# v2_1.net
KiCad netlist of a schematic drawn in EAGLE
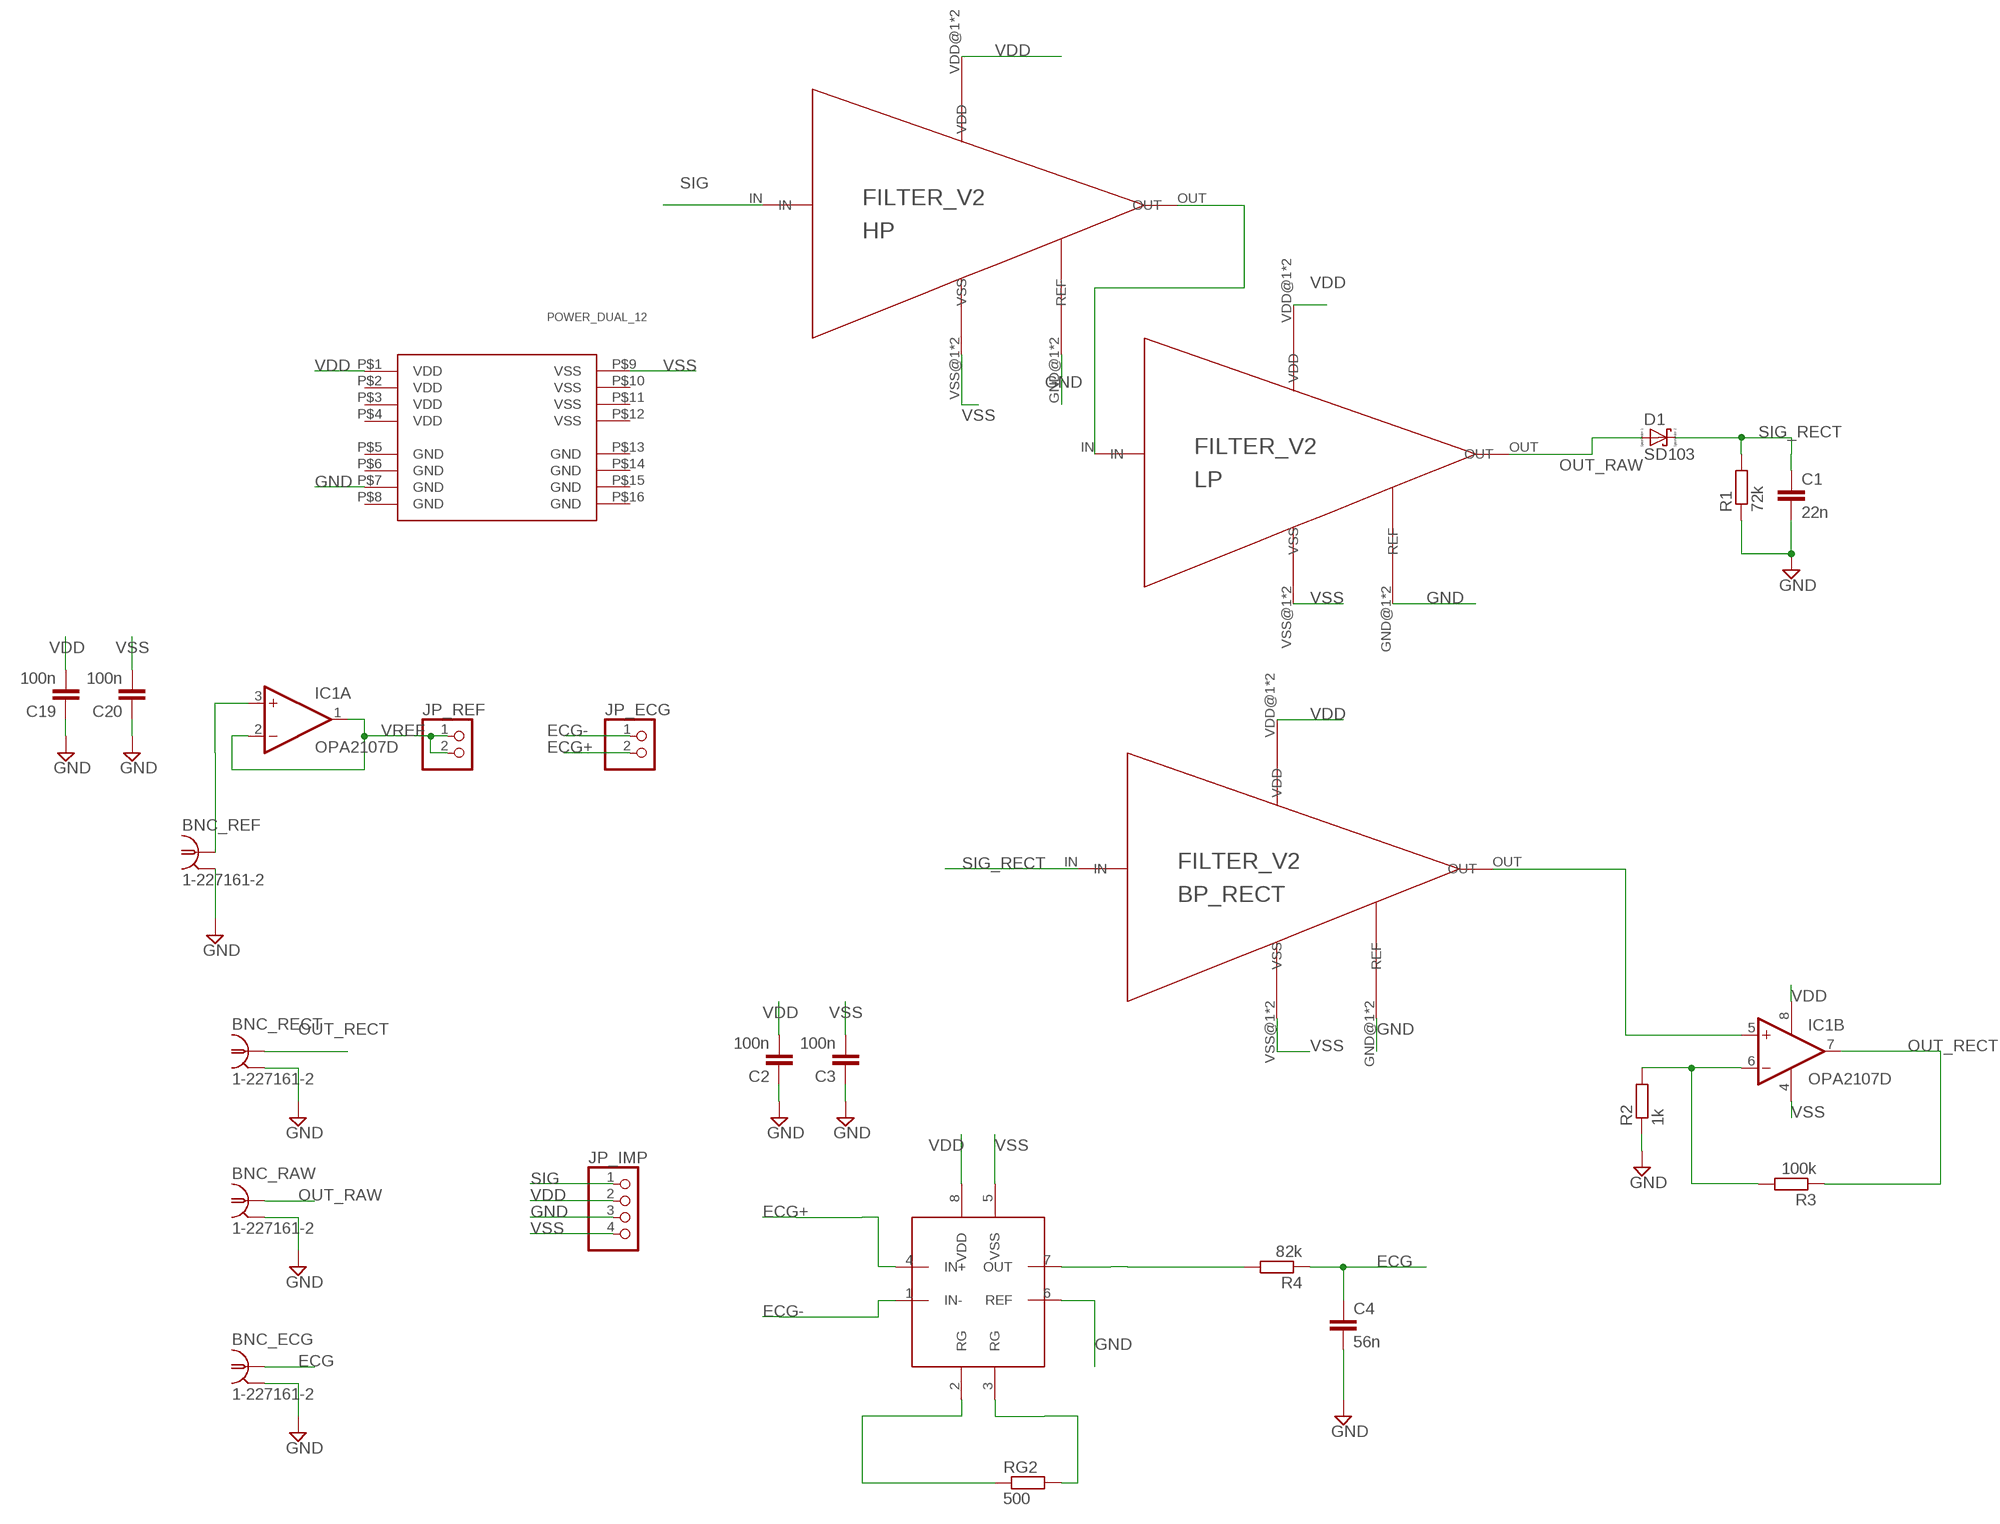
[diagram p0: schematic, sheet 1]

(export (version "E")
  (design (tool "Eeschema 10.0.6"))
  (components
    (comp (ref "BNC_ECG")
      (value "1-227161-2")
      (footprint "eagle-import:AMP_227161")
      (libsource (lib "eagle-import") (part "?2271611--2"))
    )
    (comp (ref "BNC_RAW")
      (value "1-227161-2")
      (footprint "eagle-import:AMP_227161")
      (libsource (lib "eagle-import") (part "?2271611--2"))
    )
    (comp (ref "BNC_RECT")
      (value "1-227161-2")
      (footprint "eagle-import:AMP_227161")
      (libsource (lib "eagle-import") (part "?2271611--2"))
    )
    (comp (ref "BNC_REF")
      (value "1-227161-2")
      (footprint "eagle-import:AMP_227161")
      (libsource (lib "eagle-import") (part "?2271611--2"))
    )
    (comp (ref "BP_RECT")
      (value "FILTER_V2")
      (footprint "eagle-import:MODULE_FILTER_V2")
      (libsource (lib "eagle-import") (part "FILTER_V2"))
    )
    (comp (ref "C1")
      (value "22n")
      (footprint "eagle-import:C0805")
      (libsource (lib "eagle-import") (part "C-EUC0805"))
    )
    (comp (ref "C2")
      (value "100n")
      (footprint "eagle-import:C0805")
      (libsource (lib "eagle-import") (part "resistor_348_C-EUC0805"))
    )
    (comp (ref "C3")
      (value "100n")
      (footprint "eagle-import:C0805")
      (libsource (lib "eagle-import") (part "resistor_348_C-EUC0805"))
    )
    (comp (ref "C4")
      (value "56n")
      (footprint "eagle-import:C0805")
      (libsource (lib "eagle-import") (part "C-EUC0805"))
    )
    (comp (ref "C19")
      (value "100n")
      (footprint "eagle-import:C0805")
      (libsource (lib "eagle-import") (part "resistor_348_C-EUC0805"))
    )
    (comp (ref "C20")
      (value "100n")
      (footprint "eagle-import:C0805")
      (libsource (lib "eagle-import") (part "resistor_348_C-EUC0805"))
    )
    (comp (ref "D1")
      (value "SD103")
      (footprint "eagle-import:DIODE_SMB")
      (libsource (lib "eagle-import") (part "SCHOTTKY-DIODE"))
    )
    (comp (ref "HP")
      (value "FILTER_V2")
      (footprint "eagle-import:MODULE_FILTER_V2")
      (libsource (lib "eagle-import") (part "FILTER_V2"))
    )
    (comp (ref "IC1")
      (value "OPA2107D")
      (footprint "eagle-import:SO08")
      (libsource (lib "eagle-import") (part "OPA2107D"))
    )
    (comp (ref "INA")
      (value "AD8429")
      (footprint "eagle-import:SO8")
      (libsource (lib "eagle-import") (part "AD8429"))
    )
    (comp (ref "JP_ECG")
      (value "PINHD-1X2")
      (footprint "eagle-import:1X02")
      (libsource (lib "eagle-import") (part "PINHD-1X2"))
    )
    (comp (ref "JP_IMP")
      (value "PINHD-1X4")
      (footprint "eagle-import:1X04")
      (libsource (lib "eagle-import") (part "PINHD-1X4"))
    )
    (comp (ref "JP_REF")
      (value "PINHD-1X2")
      (footprint "eagle-import:1X02")
      (libsource (lib "eagle-import") (part "PINHD-1X2"))
    )
    (comp (ref "LP")
      (value "FILTER_V2")
      (footprint "eagle-import:MODULE_FILTER_V2")
      (libsource (lib "eagle-import") (part "FILTER_V2"))
    )
    (comp (ref "R1")
      (value "72k")
      (footprint "eagle-import:R0805")
      (libsource (lib "eagle-import") (part "R-EU_R0805"))
    )
    (comp (ref "R2")
      (value "1k")
      (footprint "eagle-import:R0805")
      (libsource (lib "eagle-import") (part "R-EU_R0805"))
    )
    (comp (ref "R3")
      (value "100k")
      (footprint "eagle-import:R0805")
      (libsource (lib "eagle-import") (part "R-EU_R0805"))
    )
    (comp (ref "R4")
      (value "82k")
      (footprint "eagle-import:R0805")
      (libsource (lib "eagle-import") (part "R-EU_R0805"))
    )
    (comp (ref "RG2")
      (value "500")
      (footprint "eagle-import:R0805")
      (libsource (lib "eagle-import") (part "R-EU_R0805"))
    )
    (comp (ref "U$1")
      (value "POWER_DUAL_12")
      (footprint "eagle-import:MODULE_4X8")
      (libsource (lib "eagle-import") (part "POWER_DUAL_12"))
    )
  )
  (nets
    (net (code "1") (name "/ECG") (class "Default")
      (node (ref "BNC_ECG") (pin "1") (pinfunction "1_1") (pintype "passive"))
      (node (ref "C4") (pin "1") (pinfunction "1_1") (pintype "passive"))
      (node (ref "R4") (pin "1") (pinfunction "1_1") (pintype "passive"))
    )
    (net (code "2") (name "/ECG+") (class "Default")
      (node (ref "INA") (pin "4") (pinfunction "IN+_4") (pintype "bidirectional"))
      (node (ref "JP_ECG") (pin "2") (pinfunction "2_2") (pintype "passive"))
    )
    (net (code "3") (name "/ECG-") (class "Default")
      (node (ref "INA") (pin "1") (pinfunction "IN-_1") (pintype "bidirectional"))
      (node (ref "JP_ECG") (pin "1") (pinfunction "1_1") (pintype "passive"))
    )
    (net (code "4") (name "/OUT_RAW") (class "Default")
      (node (ref "BNC_RAW") (pin "1") (pinfunction "1_1") (pintype "passive"))
      (node (ref "D1") (pin "A") (pinfunction "C_A") (pintype "passive"))
      (node (ref "LP") (pin "OUT") (pinfunction "OUT_OUT") (pintype "bidirectional"))
    )
    (net (code "5") (name "/OUT_RECT") (class "Default")
      (node (ref "BNC_RECT") (pin "1") (pinfunction "1_1") (pintype "passive"))
      (node (ref "IC1") (pin "7") (pinfunction "OUT_7") (pintype "output"))
      (node (ref "R3") (pin "1") (pinfunction "1_1") (pintype "passive"))
    )
    (net (code "6") (name "/SIG") (class "Default")
      (node (ref "HP") (pin "IN") (pinfunction "IN_IN") (pintype "bidirectional"))
      (node (ref "JP_IMP") (pin "1") (pinfunction "1_1") (pintype "passive"))
    )
    (net (code "7") (name "/SIG_RECT") (class "Default")
      (node (ref "BP_RECT") (pin "IN") (pinfunction "IN_IN") (pintype "bidirectional"))
      (node (ref "C1") (pin "1") (pinfunction "1_1") (pintype "passive"))
      (node (ref "D1") (pin "C") (pinfunction "A_C") (pintype "passive"))
      (node (ref "R1") (pin "2") (pinfunction "2_2") (pintype "passive"))
    )
    (net (code "8") (name "/VDD") (class "Default")
      (node (ref "BP_RECT") (pin "VDD@1") (pinfunction "VDD_VDD@1") (pintype "bidirectional"))
      (node (ref "BP_RECT") (pin "VDD@2") (pinfunction "VDD_VDD@2") (pintype "bidirectional"))
      (node (ref "C19") (pin "2") (pinfunction "2_2") (pintype "passive"))
      (node (ref "C2") (pin "2") (pinfunction "2_2") (pintype "passive"))
      (node (ref "HP") (pin "VDD@1") (pinfunction "VDD_VDD@1") (pintype "bidirectional"))
      (node (ref "HP") (pin "VDD@2") (pinfunction "VDD_VDD@2") (pintype "bidirectional"))
      (node (ref "IC1") (pin "8") (pinfunction "V+_8") (pintype "power_in"))
      (node (ref "INA") (pin "8") (pinfunction "VDD_8") (pintype "bidirectional"))
      (node (ref "JP_IMP") (pin "2") (pinfunction "2_2") (pintype "passive"))
      (node (ref "LP") (pin "VDD@1") (pinfunction "VDD_VDD@1") (pintype "bidirectional"))
      (node (ref "LP") (pin "VDD@2") (pinfunction "VDD_VDD@2") (pintype "bidirectional"))
      (node (ref "U$1") (pin "P$1") (pinfunction "VDD_P$1") (pintype "bidirectional"))
    )
    (net (code "9") (name "/VREF") (class "Default")
      (node (ref "IC1") (pin "1") (pinfunction "OUT_1") (pintype "output"))
      (node (ref "IC1") (pin "2") (pinfunction "-IN_2") (pintype "input"))
      (node (ref "JP_REF") (pin "1") (pinfunction "1_1") (pintype "passive"))
      (node (ref "JP_REF") (pin "2") (pinfunction "2_2") (pintype "passive"))
    )
    (net (code "10") (name "/VSS") (class "Default")
      (node (ref "BP_RECT") (pin "VSS@1") (pinfunction "VSS_VSS@1") (pintype "bidirectional"))
      (node (ref "BP_RECT") (pin "VSS@2") (pinfunction "VSS_VSS@2") (pintype "bidirectional"))
      (node (ref "C20") (pin "2") (pinfunction "2_2") (pintype "passive"))
      (node (ref "C3") (pin "2") (pinfunction "2_2") (pintype "passive"))
      (node (ref "HP") (pin "VSS@1") (pinfunction "VSS_VSS@1") (pintype "bidirectional"))
      (node (ref "HP") (pin "VSS@2") (pinfunction "VSS_VSS@2") (pintype "bidirectional"))
      (node (ref "IC1") (pin "4") (pinfunction "V-_4") (pintype "power_in"))
      (node (ref "INA") (pin "5") (pinfunction "VSS_5") (pintype "bidirectional"))
      (node (ref "JP_IMP") (pin "4") (pinfunction "4_4") (pintype "passive"))
      (node (ref "LP") (pin "VSS@1") (pinfunction "VSS_VSS@1") (pintype "bidirectional"))
      (node (ref "LP") (pin "VSS@2") (pinfunction "VSS_VSS@2") (pintype "bidirectional"))
      (node (ref "U$1") (pin "P$9") (pinfunction "VSS_P$9") (pintype "bidirectional"))
    )
    (net (code "11") (name "GND") (class "Default")
      (node (ref "BNC_ECG") (pin "2") (pinfunction "2_2") (pintype "passive"))
      (node (ref "BNC_RAW") (pin "2") (pinfunction "2_2") (pintype "passive"))
      (node (ref "BNC_RECT") (pin "2") (pinfunction "2_2") (pintype "passive"))
      (node (ref "BNC_REF") (pin "2") (pinfunction "2_2") (pintype "passive"))
      (node (ref "BP_RECT") (pin "GND@1") (pinfunction "REF_GND@1") (pintype "bidirectional"))
      (node (ref "BP_RECT") (pin "GND@2") (pinfunction "REF_GND@2") (pintype "bidirectional"))
      (node (ref "C1") (pin "2") (pinfunction "2_2") (pintype "passive"))
      (node (ref "C19") (pin "1") (pinfunction "1_1") (pintype "passive"))
      (node (ref "C2") (pin "1") (pinfunction "1_1") (pintype "passive"))
      (node (ref "C20") (pin "1") (pinfunction "1_1") (pintype "passive"))
      (node (ref "C3") (pin "1") (pinfunction "1_1") (pintype "passive"))
      (node (ref "C4") (pin "2") (pinfunction "2_2") (pintype "passive"))
      (node (ref "HP") (pin "GND@1") (pinfunction "REF_GND@1") (pintype "bidirectional"))
      (node (ref "HP") (pin "GND@2") (pinfunction "REF_GND@2") (pintype "bidirectional"))
      (node (ref "INA") (pin "6") (pinfunction "REF_6") (pintype "bidirectional"))
      (node (ref "JP_IMP") (pin "3") (pinfunction "3_3") (pintype "passive"))
      (node (ref "LP") (pin "GND@1") (pinfunction "REF_GND@1") (pintype "bidirectional"))
      (node (ref "LP") (pin "GND@2") (pinfunction "REF_GND@2") (pintype "bidirectional"))
      (node (ref "R1") (pin "1") (pinfunction "1_1") (pintype "passive"))
      (node (ref "R2") (pin "1") (pinfunction "1_1") (pintype "passive"))
      (node (ref "U$1") (pin "P$7") (pinfunction "GND_P$7") (pintype "bidirectional"))
    )
    (net (code "12") (name "Net-(HP-PadOUT)") (class "Default")
      (node (ref "HP") (pin "OUT") (pinfunction "OUT_OUT") (pintype "bidirectional"))
      (node (ref "LP") (pin "IN") (pinfunction "IN_IN") (pintype "bidirectional"))
    )
    (net (code "13") (name "Net-(IC1A-+IN)") (class "Default")
      (node (ref "BNC_REF") (pin "1") (pinfunction "1_1") (pintype "passive"))
      (node (ref "IC1") (pin "3") (pinfunction "+IN_3") (pintype "input"))
    )
    (net (code "14") (name "Net-(IC1B-+IN)") (class "Default")
      (node (ref "BP_RECT") (pin "OUT") (pinfunction "OUT_OUT") (pintype "bidirectional"))
      (node (ref "IC1") (pin "5") (pinfunction "+IN_5") (pintype "input"))
    )
    (net (code "15") (name "Net-(IC1B--IN)") (class "Default")
      (node (ref "IC1") (pin "6") (pinfunction "-IN_6") (pintype "input"))
      (node (ref "R2") (pin "2") (pinfunction "2_2") (pintype "passive"))
      (node (ref "R3") (pin "2") (pinfunction "2_2") (pintype "passive"))
    )
    (net (code "16") (name "Net-(INA-OUT)") (class "Default")
      (node (ref "INA") (pin "7") (pinfunction "OUT_7") (pintype "bidirectional"))
      (node (ref "R4") (pin "2") (pinfunction "2_2") (pintype "passive"))
    )
    (net (code "17") (name "Net-(INA-RG-Pad2)") (class "Default")
      (node (ref "INA") (pin "2") (pinfunction "RG_2") (pintype "bidirectional"))
      (node (ref "RG2") (pin "1") (pinfunction "1_1") (pintype "passive"))
    )
    (net (code "18") (name "Net-(INA-RG-Pad3)") (class "Default")
      (node (ref "INA") (pin "3") (pinfunction "RG_3") (pintype "bidirectional"))
      (node (ref "RG2") (pin "2") (pinfunction "2_2") (pintype "passive"))
    )
    (net (code "19") (name "unconnected-(U$1-GND-PadP$5)") (class "Default")
      (node (ref "U$1") (pin "P$5") (pinfunction "GND_P$5") (pintype "bidirectional"))
    )
    (net (code "20") (name "unconnected-(U$1-GND-PadP$6)") (class "Default")
      (node (ref "U$1") (pin "P$6") (pinfunction "GND_P$6") (pintype "bidirectional"))
    )
    (net (code "21") (name "unconnected-(U$1-GND-PadP$8)") (class "Default")
      (node (ref "U$1") (pin "P$8") (pinfunction "GND_P$8") (pintype "bidirectional"))
    )
    (net (code "22") (name "unconnected-(U$1-GND-PadP$13)") (class "Default")
      (node (ref "U$1") (pin "P$13") (pinfunction "GND_P$13") (pintype "bidirectional"))
    )
    (net (code "23") (name "unconnected-(U$1-GND-PadP$14)") (class "Default")
      (node (ref "U$1") (pin "P$14") (pinfunction "GND_P$14") (pintype "bidirectional"))
    )
    (net (code "24") (name "unconnected-(U$1-GND-PadP$15)") (class "Default")
      (node (ref "U$1") (pin "P$15") (pinfunction "GND_P$15") (pintype "bidirectional"))
    )
    (net (code "25") (name "unconnected-(U$1-GND-PadP$16)") (class "Default")
      (node (ref "U$1") (pin "P$16") (pinfunction "GND_P$16") (pintype "bidirectional"))
    )
    (net (code "26") (name "unconnected-(U$1-VDD-PadP$2)") (class "Default")
      (node (ref "U$1") (pin "P$2") (pinfunction "VDD_P$2") (pintype "bidirectional"))
    )
    (net (code "27") (name "unconnected-(U$1-VDD-PadP$3)") (class "Default")
      (node (ref "U$1") (pin "P$3") (pinfunction "VDD_P$3") (pintype "bidirectional"))
    )
    (net (code "28") (name "unconnected-(U$1-VDD-PadP$4)") (class "Default")
      (node (ref "U$1") (pin "P$4") (pinfunction "VDD_P$4") (pintype "bidirectional"))
    )
    (net (code "29") (name "unconnected-(U$1-VSS-PadP$10)") (class "Default")
      (node (ref "U$1") (pin "P$10") (pinfunction "VSS_P$10") (pintype "bidirectional"))
    )
    (net (code "30") (name "unconnected-(U$1-VSS-PadP$11)") (class "Default")
      (node (ref "U$1") (pin "P$11") (pinfunction "VSS_P$11") (pintype "bidirectional"))
    )
    (net (code "31") (name "unconnected-(U$1-VSS-PadP$12)") (class "Default")
      (node (ref "U$1") (pin "P$12") (pinfunction "VSS_P$12") (pintype "bidirectional"))
    )
  )
)
